# PicoCore-S3.net
KiCad netlist of a schematic drawn in Altium Designer
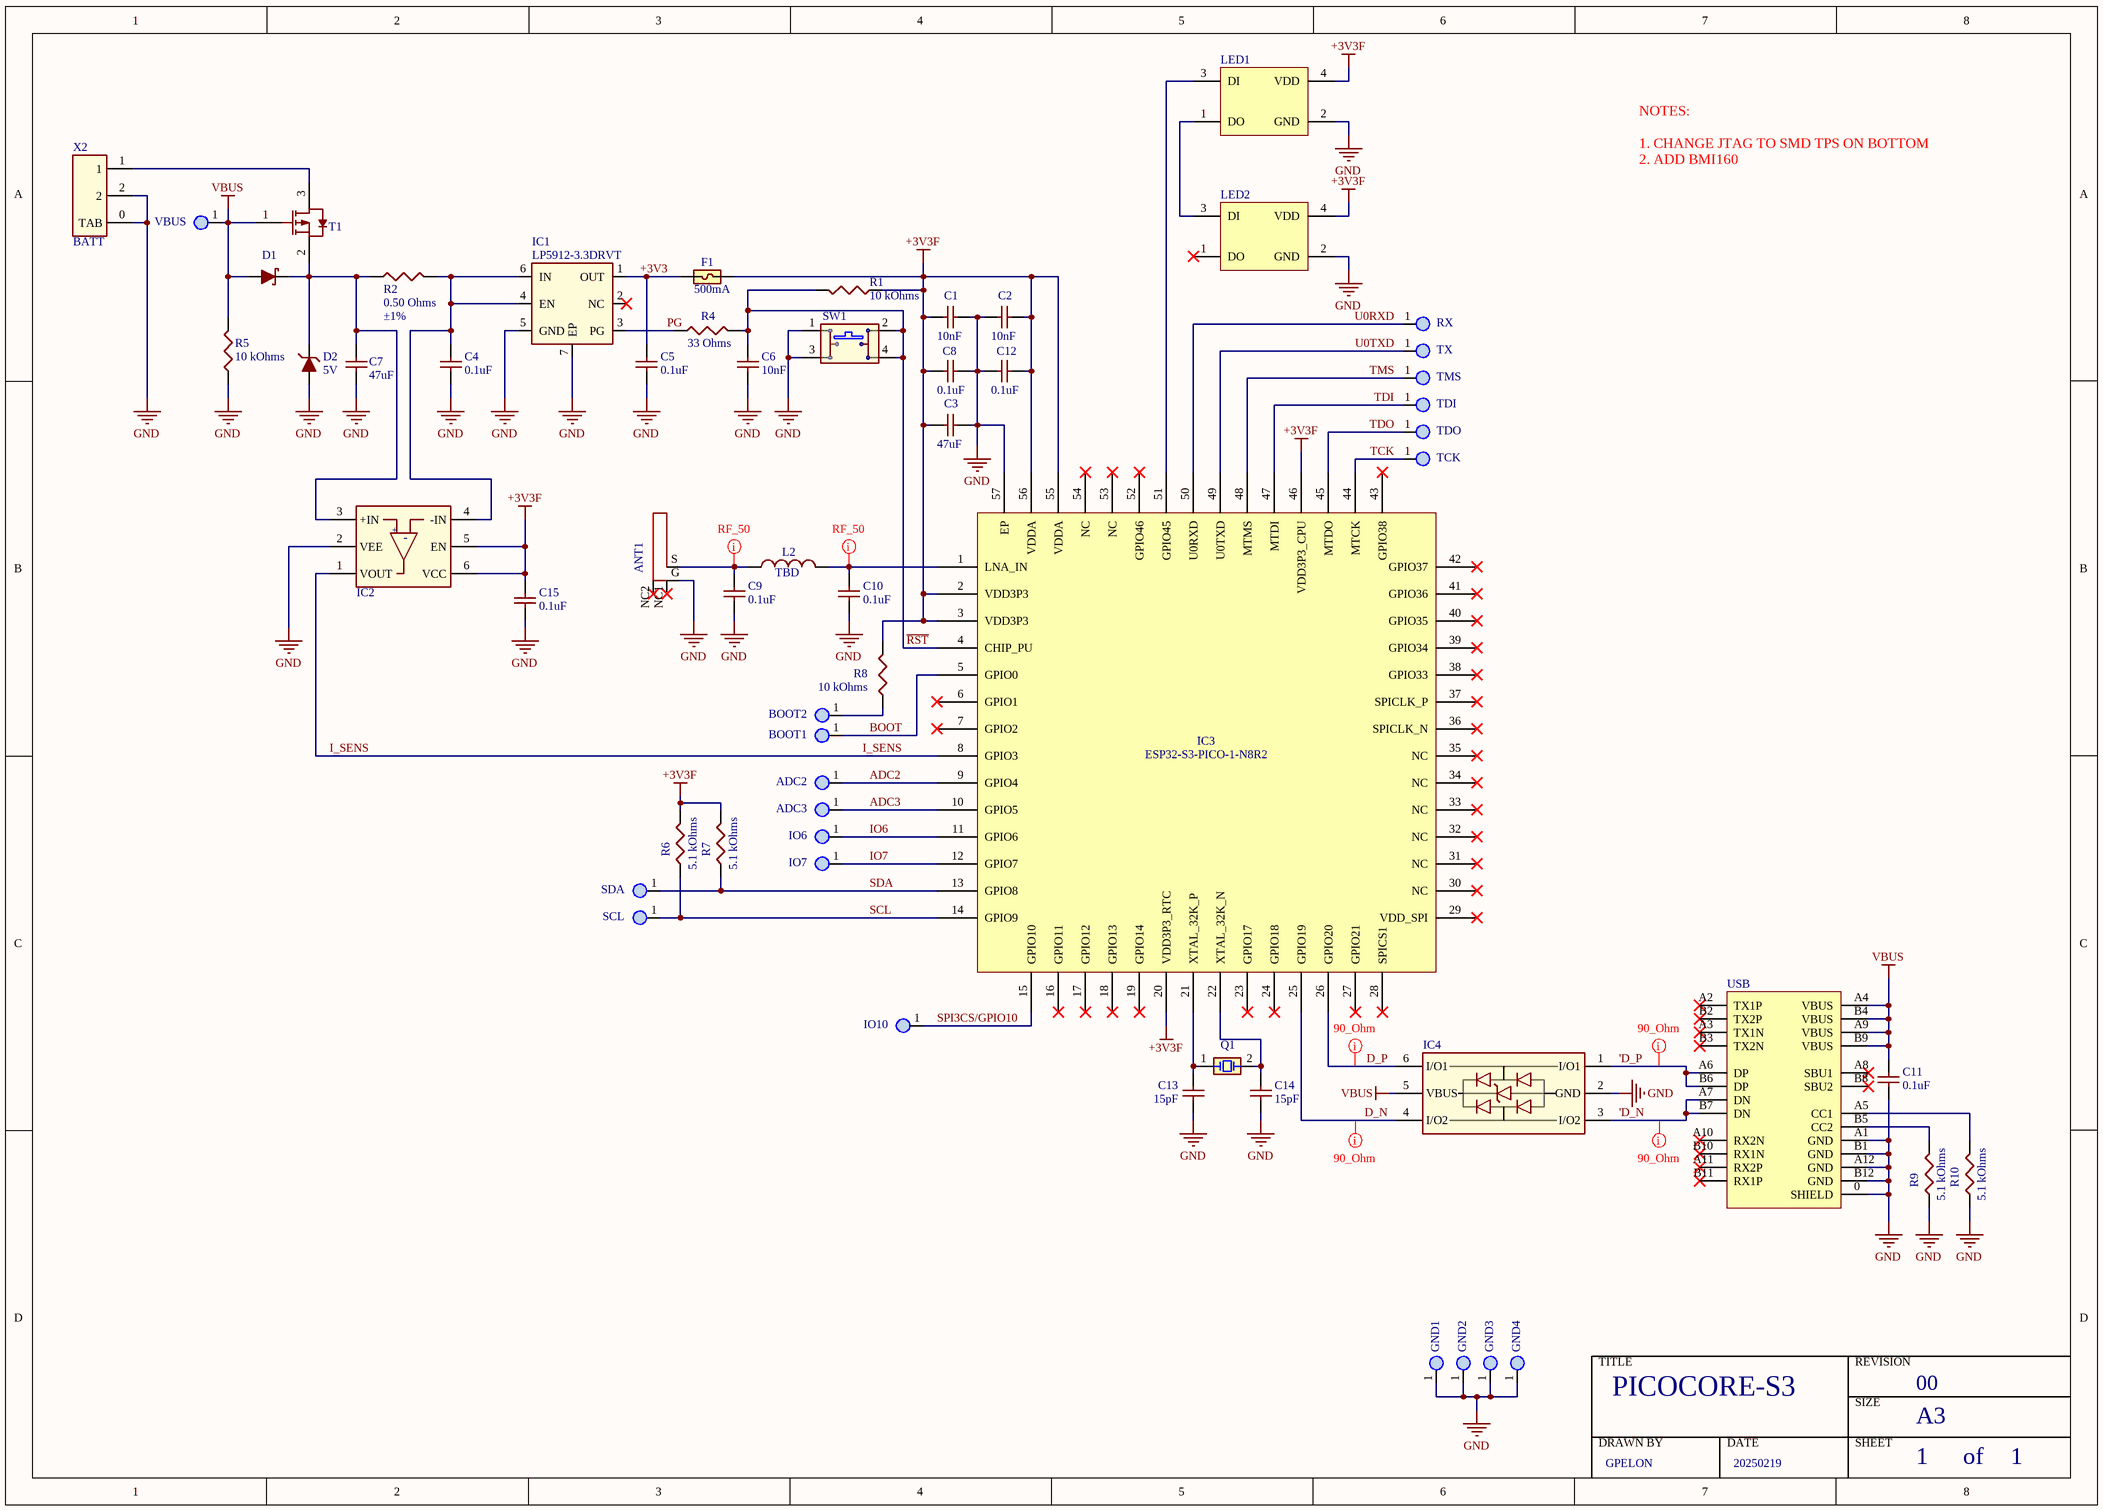
[diagram p0: PicoCore-S3.SchDoc]

(export (version "E")
  (design (tool "Eeschema 10.0.6"))
  (components
    (comp (ref "ADC2")
      (value "CASTELLATED PAD")
      (footprint "CASTELLATED PAD")
      (libsource (lib "PICOCORE-S3") (part "CASTELLATED_PAD"))
    )
    (comp (ref "ADC3")
      (value "CASTELLATED PAD")
      (footprint "CASTELLATED PAD")
      (libsource (lib "PICOCORE-S3") (part "CASTELLATED_PAD"))
    )
    (comp (ref "ANT1")
      (value "RF ANT 2.4GHZ STAMPED MET SLD")
      (footprint "PRO-OB-440")
      (description "RF ANTENNA Bluetooth, WirelessHART, WLAN, Zigbee™ Stamped Metal Solder Surface Mount")
      (fields (field (name "PRIMARY MANUFACTURER PART NUMBER") "PRO-OB-440"))
      (libsource (lib "PICOCORE-S3") (part "PRO-OB-440"))
    )
    (comp (ref "BOOT1")
      (value "CASTELLATED PAD")
      (footprint "CASTELLATED PAD")
      (libsource (lib "PICOCORE-S3") (part "CASTELLATED_PAD"))
    )
    (comp (ref "BOOT2")
      (value "CASTELLATED PAD")
      (footprint "CASTELLATED PAD")
      (libsource (lib "PICOCORE-S3") (part "CASTELLATED_PAD"))
    )
    (comp (ref "C1")
      (value "CAP NP")
      (footprint "CAP_0402_IPC")
      (description "CAP CER 10nF 10% 50V X7R 0402")
      (fields
        (field (name "PRIMARY MANUFACTURER PART NUMBER") "CGA2B3X7R1H103K050BB")
        (field (name "METHODE PART NUMBER") "18191XA86")
        (field (name "ELECTRICAL VALUE") "10nF")
      )
      (libsource (lib "MIL_DATABASE") (part "CAP NP"))
    )
    (comp (ref "C2")
      (value "CAP NP")
      (footprint "CAP_0402_IPC")
      (description "CAP CER 10nF 10% 50V X7R 0402")
      (fields
        (field (name "PRIMARY MANUFACTURER PART NUMBER") "CGA2B3X7R1H103K050BB")
        (field (name "METHODE PART NUMBER") "18191XA86")
        (field (name "ELECTRICAL VALUE") "10nF")
      )
      (libsource (lib "MIL_DATABASE") (part "CAP NP"))
    )
    (comp (ref "C3")
      (value "CAP NP")
      (footprint "CAP_1206_IPC")
      (description "Capacitor Ceramic 47UF 25V 20% X5R 1206")
      (fields
        (field (name "PRIMARY MANUFACTURER PART NUMBER") "C3216X5R1E476M160AC")
        (field (name "METHODE PART NUMBER") "TBD")
        (field (name "ELECTRICAL VALUE") "47uF")
      )
      (libsource (lib "MIL_DATABASE") (part "CAP NP"))
    )
    (comp (ref "C4")
      (value "CAP NP")
      (footprint "CAP_0402_IPC")
      (description "CAP CER 0.1uF 10% 50V X7R 0402")
      (fields
        (field (name "PRIMARY MANUFACTURER PART NUMBER") "GCM155R71H104KE02D")
        (field (name "METHODE PART NUMBER") "18191XA98")
        (field (name "ELECTRICAL VALUE") "0.1uF")
      )
      (libsource (lib "MIL_DATABASE") (part "CAP NP"))
    )
    (comp (ref "C5")
      (value "CAP NP")
      (footprint "CAP_0402_IPC")
      (description "CAP CER 0.1uF 10% 50V X7R 0402")
      (fields
        (field (name "PRIMARY MANUFACTURER PART NUMBER") "GCM155R71H104KE02D")
        (field (name "METHODE PART NUMBER") "18191XA98")
        (field (name "ELECTRICAL VALUE") "0.1uF")
      )
      (libsource (lib "MIL_DATABASE") (part "CAP NP"))
    )
    (comp (ref "C6")
      (value "CAP NP")
      (footprint "CAP_0402_IPC")
      (description "CAP CER 10nF 10% 50V X7R 0402")
      (fields
        (field (name "PRIMARY MANUFACTURER PART NUMBER") "CGA2B3X7R1H103K050BB")
        (field (name "METHODE PART NUMBER") "18191XA86")
        (field (name "ELECTRICAL VALUE") "10nF")
      )
      (libsource (lib "MIL_DATABASE") (part "CAP NP"))
    )
    (comp (ref "C7")
      (value "CAP NP")
      (footprint "CAP_1206_IPC")
      (description "Capacitor Ceramic 47UF 25V 20% X5R 1206")
      (fields
        (field (name "PRIMARY MANUFACTURER PART NUMBER") "C3216X5R1E476M160AC")
        (field (name "METHODE PART NUMBER") "TBD")
        (field (name "ELECTRICAL VALUE") "47uF")
      )
      (libsource (lib "MIL_DATABASE") (part "CAP NP"))
    )
    (comp (ref "C8")
      (value "CAP NP")
      (footprint "CAP_0402_IPC")
      (description "CAP CER 0.1uF 10% 50V X7R 0402")
      (fields
        (field (name "PRIMARY MANUFACTURER PART NUMBER") "GCM155R71H104KE02D")
        (field (name "METHODE PART NUMBER") "18191XA98")
        (field (name "ELECTRICAL VALUE") "0.1uF")
      )
      (libsource (lib "MIL_DATABASE") (part "CAP NP"))
    )
    (comp (ref "C9")
      (value "CAP NP")
      (footprint "CAP_0402_IPC")
      (description "CAP CER 0.1uF 10% 50V X7R 0402")
      (fields
        (field (name "PRIMARY MANUFACTURER PART NUMBER") "GCM155R71H104KE02D")
        (field (name "METHODE PART NUMBER") "18191XA98")
        (field (name "ELECTRICAL VALUE") "0.1uF")
      )
      (libsource (lib "MIL_DATABASE") (part "CAP NP"))
    )
    (comp (ref "C10")
      (value "CAP NP")
      (footprint "CAP_0402_IPC")
      (description "CAP CER 0.1uF 10% 50V X7R 0402")
      (fields
        (field (name "PRIMARY MANUFACTURER PART NUMBER") "GCM155R71H104KE02D")
        (field (name "METHODE PART NUMBER") "18191XA98")
        (field (name "ELECTRICAL VALUE") "0.1uF")
      )
      (libsource (lib "MIL_DATABASE") (part "CAP NP"))
    )
    (comp (ref "C11")
      (value "CAP NP")
      (footprint "CAP_0402_IPC")
      (description "CAP CER 0.1uF 10% 50V X7R 0402")
      (fields
        (field (name "PRIMARY MANUFACTURER PART NUMBER") "GCM155R71H104KE02D")
        (field (name "METHODE PART NUMBER") "18191XA98")
        (field (name "ELECTRICAL VALUE") "0.1uF")
      )
      (libsource (lib "MIL_DATABASE") (part "CAP NP"))
    )
    (comp (ref "C12")
      (value "CAP NP")
      (footprint "CAP_0402_IPC")
      (description "CAP CER 0.1uF 10% 50V X7R 0402")
      (fields
        (field (name "PRIMARY MANUFACTURER PART NUMBER") "GCM155R71H104KE02D")
        (field (name "METHODE PART NUMBER") "18191XA98")
        (field (name "ELECTRICAL VALUE") "0.1uF")
      )
      (libsource (lib "MIL_DATABASE") (part "CAP NP"))
    )
    (comp (ref "C13")
      (value "CAP NP")
      (footprint "CAP_0603_IPC")
      (description "Capacitor Ceramic NPO, SMT, 15PF, 50V, 5%, 0603")
      (fields
        (field (name "PRIMARY MANUFACTURER PART NUMBER") "C0603C150J5GACTU")
        (field (name "ELECTRICAL VALUE") "15pF")
      )
      (libsource (lib "MIL_DATABASE") (part "CAP NP"))
    )
    (comp (ref "C14")
      (value "CAP NP")
      (footprint "CAP_0603_IPC")
      (description "Capacitor Ceramic NPO, SMT, 15PF, 50V, 5%, 0603")
      (fields
        (field (name "PRIMARY MANUFACTURER PART NUMBER") "C0603C150J5GACTU")
        (field (name "ELECTRICAL VALUE") "15pF")
      )
      (libsource (lib "MIL_DATABASE") (part "CAP NP"))
    )
    (comp (ref "C15")
      (value "CAP NP")
      (footprint "CAP_0402_IPC")
      (description "CAP CER 0.1uF 10% 50V X7R 0402")
      (fields
        (field (name "PRIMARY MANUFACTURER PART NUMBER") "GCM155R71H104KE02D")
        (field (name "METHODE PART NUMBER") "18191XA98")
        (field (name "ELECTRICAL VALUE") "0.1uF")
      )
      (libsource (lib "MIL_DATABASE") (part "CAP NP"))
    )
    (comp (ref "D1")
      (value "DIODE_SCHOTTKY")
      (footprint "SOD-123_IPC")
      (description "DIODE SCHOTTKY 40V 500MA SOD123")
      (fields
        (field (name "PRIMARY MANUFACTURER PART NUMBER") "MBR0540-TP")
        (field (name "METHODE PART NUMBER") "TBD")
      )
      (libsource (lib "MIL_DATABASE") (part "DIODE_SCHOTTKY"))
    )
    (comp (ref "D2")
      (value "DIODE_TVS_UNI")
      (footprint "SOD-523_IPC")
      (description "Zener Diode, SMT, TVS, ESD, 5.0V, SOD-523")
      (fields
        (field (name "PRIMARY MANUFACTURER PART NUMBER") "ESD5Z5.0T1G")
        (field (name "METHODE PART NUMBER") "16441XA7")
        (field (name "ELECTRICAL VALUE") "5V")
      )
      (libsource (lib "MIL_DATABASE") (part "DIODE_TVS_UNI"))
    )
    (comp (ref "F1")
      (value "FUSE")
      (footprint "PTC_1206_IPC")
      (description "PTC RESET FUSE 24V 500MA 1206")
      (fields
        (field (name "PRIMARY MANUFACTURER PART NUMBER") "0ZCJ0050AF2E")
        (field (name "METHODE PART NUMBER") "TBD")
        (field (name "RATING1 VALUE") "500mA")
      )
      (libsource (lib "MIL_DATABASE") (part "FUSE"))
    )
    (comp (ref "GND1")
      (value "CASTELLATED PAD")
      (footprint "CASTELLATED PAD")
      (libsource (lib "PICOCORE-S3") (part "CASTELLATED_PAD"))
    )
    (comp (ref "GND2")
      (value "CASTELLATED PAD")
      (footprint "CASTELLATED PAD")
      (libsource (lib "PICOCORE-S3") (part "CASTELLATED_PAD"))
    )
    (comp (ref "GND3")
      (value "CASTELLATED PAD")
      (footprint "CASTELLATED PAD")
      (libsource (lib "PICOCORE-S3") (part "CASTELLATED_PAD"))
    )
    (comp (ref "GND4")
      (value "CASTELLATED PAD")
      (footprint "CASTELLATED PAD")
      (libsource (lib "PICOCORE-S3") (part "CASTELLATED_PAD"))
    )
    (comp (ref "IC1")
      (value "LP5912-3.3")
      (footprint "SON6_0P65_EP_IPC")
      (description "IC REG LDO 3.3V 0.5A 6SON")
      (fields
        (field (name "PRIMARY MANUFACTURER PART NUMBER") "LP5912-3.3DRVT")
        (field (name "METHODE PART NUMBER") "TBD")
      )
      (libsource (lib "MIL_DATABASE") (part "LP5912-3.3"))
    )
    (comp (ref "IC2")
      (value "NCV2002SN2T1")
      (footprint "TSOP6_0P95_IPC")
      (description "IC OPAMP 1-CIRCUIT RAIL-TO-RAIL TSOP-6")
      (fields
        (field (name "PRIMARY MANUFACTURER PART NUMBER") "NCV2002SN2T1G")
        (field (name "METHODE PART NUMBER") "16455XA64")
      )
      (libsource (lib "MIL_DATABASE") (part "NCV2002SN2T1"))
    )
    (comp (ref "IC3")
      (value "RF TXRX MOD BLUETOOTH WIFISMD")
      (footprint "LGA56")
      (fields (field (name "PRIMARY MANUFACTURER PART NUMBER") "ESP32-S3-PICO-1-N8R2"))
      (libsource (lib "PICOCORE-S3") (part "ESP32-S3-PICO-1-N8R2"))
    )
    (comp (ref "IC4")
      (value "USBLC6-2P6")
      (footprint "SOT666_IPC")
      (description "TVS DIODE 5.25V 17VC SOT-666")
      (fields (field (name "METHODE PART NUMBER") "TBD"))
      (libsource (lib "MIL_DATABASE") (part "USBLC6-2P6"))
    )
    (comp (ref "IO6")
      (value "CASTELLATED PAD")
      (footprint "CASTELLATED PAD")
      (libsource (lib "PICOCORE-S3") (part "CASTELLATED_PAD"))
    )
    (comp (ref "IO7")
      (value "CASTELLATED PAD")
      (footprint "CASTELLATED PAD")
      (libsource (lib "PICOCORE-S3") (part "CASTELLATED_PAD"))
    )
    (comp (ref "IO10")
      (value "CASTELLATED PAD")
      (footprint "CASTELLATED PAD")
      (libsource (lib "PICOCORE-S3") (part "CASTELLATED_PAD"))
    )
    (comp (ref "L2")
      (value "TBD")
      (footprint "IND_0805_IPC")
      (description "CHIP BEAD 1K OHM 600mA 0805")
      (fields (field (name "PRIMARY MANUFACTURER PART NUMBER") "BLM21AG102SN1D"))
      (libsource (lib "MIL_DATABASE") (part "IND"))
    )
    (comp (ref "LED1")
      (value "ADDRESS LED DISCRETE RGB")
      (footprint "WS2812B-2020")
      (description "Addressable Lighting Neopixel 10 LED Discrete Red, Green, Blue (RGB) 2.00mm L x 2.00mm W")
      (libsource (lib "PICOCORE-S3") (part "WS2812B-2020"))
    )
    (comp (ref "LED2")
      (value "ADDRESS LED DISCRETE RGB")
      (footprint "WS2812B-2020")
      (description "Addressable Lighting Neopixel 10 LED Discrete Red, Green, Blue (RGB) 2.00mm L x 2.00mm W")
      (libsource (lib "PICOCORE-S3") (part "WS2812B-2020"))
    )
    (comp (ref "Q1")
      (value "CRYSTAL_H_2PIN")
      (footprint "XTAL_ECX-34Q")
      (description "CRYSTAL 32.768KHZ 12.5PF SMD-2")
      (fields
        (field (name "PRIMARY MANUFACTURER PART NUMBER") "ECS-.327-12.5-34R-C-TR")
        (field (name "METHODE PART NUMBER") "TBD")
      )
      (libsource (lib "MIL_DATABASE") (part "CRYSTAL_H_2PIN"))
    )
    (comp (ref "R1")
      (value "RES")
      (footprint "RES_0402_IPC")
      (description "RES SMD 10K OHM 1% 1/16W 0402")
      (fields
        (field (name "PRIMARY MANUFACTURER PART NUMBER") "RC0402FR-0710KL")
        (field (name "METHODE PART NUMBER") "TBD")
        (field (name "ELECTRICAL VALUE") "10 kOhms")
      )
      (libsource (lib "MIL_DATABASE") (part "RES"))
    )
    (comp (ref "R2")
      (value "RES")
      (footprint "RES_1206_IPC")
      (description "RES SMD 0.250 OHM 1% 1/2W 1206")
      (fields
        (field (name "PRIMARY MANUFACTURER PART NUMBER") "CSR1206FTR500")
        (field (name "METHODE PART NUMBER") "TBD_0E24")
        (field (name "ELECTRICAL VALUE") "0.50 Ohms")
        (field (name "TOLERANCE %") "±1%")
      )
      (libsource (lib "MIL_DATABASE") (part "RES"))
    )
    (comp (ref "R4")
      (value "RES")
      (footprint "RES_0402_IPC")
      (description "RES SMD 33 OHM 1% 1/10W 0402")
      (fields
        (field (name "PRIMARY MANUFACTURER PART NUMBER") "RK73H1ETTP33R0F")
        (field (name "METHODE PART NUMBER") "TBD")
        (field (name "ELECTRICAL VALUE") "33 Ohms")
      )
      (libsource (lib "MIL_DATABASE") (part "RES"))
    )
    (comp (ref "R5")
      (value "RES")
      (footprint "RES_0402_IPC")
      (description "RES SMD 10K OHM 1% 1/16W 0402")
      (fields
        (field (name "PRIMARY MANUFACTURER PART NUMBER") "RC0402FR-0710KL")
        (field (name "METHODE PART NUMBER") "TBD")
        (field (name "ELECTRICAL VALUE") "10 kOhms")
      )
      (libsource (lib "MIL_DATABASE") (part "RES"))
    )
    (comp (ref "R6")
      (value "RES")
      (footprint "RES_0402_IPC")
      (description "RES SMD 5.1K OHM 1% 1/16W 0402")
      (fields
        (field (name "PRIMARY MANUFACTURER PART NUMBER") "RC0402FR-075K1L")
        (field (name "METHODE PART NUMBER") "TBD")
        (field (name "ELECTRICAL VALUE") "5.1 kOhms")
      )
      (libsource (lib "MIL_DATABASE") (part "RES"))
    )
    (comp (ref "R7")
      (value "RES")
      (footprint "RES_0402_IPC")
      (description "RES SMD 5.1K OHM 1% 1/16W 0402")
      (fields
        (field (name "PRIMARY MANUFACTURER PART NUMBER") "RC0402FR-075K1L")
        (field (name "METHODE PART NUMBER") "TBD")
        (field (name "ELECTRICAL VALUE") "5.1 kOhms")
      )
      (libsource (lib "MIL_DATABASE") (part "RES"))
    )
    (comp (ref "R8")
      (value "RES")
      (footprint "RES_0402_IPC")
      (description "RES SMD 10K OHM 1% 1/16W 0402")
      (fields
        (field (name "PRIMARY MANUFACTURER PART NUMBER") "RC0402FR-0710KL")
        (field (name "METHODE PART NUMBER") "TBD")
        (field (name "ELECTRICAL VALUE") "10 kOhms")
      )
      (libsource (lib "MIL_DATABASE") (part "RES"))
    )
    (comp (ref "R9")
      (value "RES")
      (footprint "RES_0402_IPC")
      (description "RES SMD 5.1K OHM 1% 1/16W 0402")
      (fields
        (field (name "PRIMARY MANUFACTURER PART NUMBER") "RC0402FR-075K1L")
        (field (name "METHODE PART NUMBER") "TBD")
        (field (name "ELECTRICAL VALUE") "5.1 kOhms")
      )
      (libsource (lib "MIL_DATABASE") (part "RES"))
    )
    (comp (ref "R10")
      (value "RES")
      (footprint "RES_0402_IPC")
      (description "RES SMD 5.1K OHM 1% 1/16W 0402")
      (fields
        (field (name "PRIMARY MANUFACTURER PART NUMBER") "RC0402FR-075K1L")
        (field (name "METHODE PART NUMBER") "TBD")
        (field (name "ELECTRICAL VALUE") "5.1 kOhms")
      )
      (libsource (lib "MIL_DATABASE") (part "RES"))
    )
    (comp (ref "RX")
      (value "CASTELLATED PAD")
      (footprint "CASTELLATED PAD")
      (libsource (lib "PICOCORE-S3") (part "CASTELLATED_PAD"))
    )
    (comp (ref "SCL")
      (value "CASTELLATED PAD")
      (footprint "CASTELLATED PAD")
      (libsource (lib "PICOCORE-S3") (part "CASTELLATED_PAD"))
    )
    (comp (ref "SDA")
      (value "CASTELLATED PAD")
      (footprint "CASTELLATED PAD")
      (libsource (lib "PICOCORE-S3") (part "CASTELLATED_PAD"))
    )
    (comp (ref "SW1")
      (value "SW-RESET")
      (footprint "SW_KMR231GLFS")
      (description "SWITCH TACTILE SPST-NO 0.05A 32V")
      (fields
        (field (name "PRIMARY MANUFACTURER PART NUMBER") "KMR231GLFS")
        (field (name "METHODE PART NUMBER") "TBD")
      )
      (libsource (lib "MIL_DATABASE") (part "SW-RESET"))
    )
    (comp (ref "T1")
      (value "MOSFET_P-CH")
      (footprint "SOT23-3_IPC")
      (description "MOSFET P-CH 20V 3.7A SOT-23")
      (fields
        (field (name "PRIMARY MANUFACTURER PART NUMBER") "IRLML6402TRPBF")
        (field (name "METHODE PART NUMBER") "TBD")
      )
      (libsource (lib "MIL_DATABASE") (part "MOSFET_P-CH"))
    )
    (comp (ref "TCK")
      (value "CASTELLATED PAD")
      (footprint "CASTELLATED PAD")
      (libsource (lib "PICOCORE-S3") (part "CASTELLATED_PAD"))
    )
    (comp (ref "TDI")
      (value "CASTELLATED PAD")
      (footprint "CASTELLATED PAD")
      (libsource (lib "PICOCORE-S3") (part "CASTELLATED_PAD"))
    )
    (comp (ref "TDO")
      (value "CASTELLATED PAD")
      (footprint "CASTELLATED PAD")
      (libsource (lib "PICOCORE-S3") (part "CASTELLATED_PAD"))
    )
    (comp (ref "TMS")
      (value "CASTELLATED PAD")
      (footprint "CASTELLATED PAD")
      (libsource (lib "PICOCORE-S3") (part "CASTELLATED_PAD"))
    )
    (comp (ref "TX")
      (value "CASTELLATED PAD")
      (footprint "CASTELLATED PAD")
      (libsource (lib "PICOCORE-S3") (part "CASTELLATED_PAD"))
    )
    (comp (ref "USB")
      (value "CONN RCP USB3.1 TYPEC 24P SMD RA")
      (footprint "12401832E402A")
      (fields (field (name "PRIMARY MANUFACTURER PART NUMBER") "12401832E402A"))
      (libsource (lib "PICOCORE-S3") (part "12401832E402A"))
    )
    (comp (ref "VBUS")
      (value "CASTELLATED PAD")
      (footprint "CASTELLATED PAD")
      (libsource (lib "PICOCORE-S3") (part "CASTELLATED_PAD"))
    )
    (comp (ref "X2")
      (value "BATT")
      (footprint "CONN_2POS_SM02B")
      (description "CONN HEADER R/A 2POS 1.25mm SMD")
      (fields
        (field (name "PRIMARY MANUFACTURER PART NUMBER") "SM02B-GHS-TB(LF)(SN)")
        (field (name "METHODE PART NUMBER") "TBD")
      )
      (libsource (lib "HET_DATABASE") (part "CONN_2POS_TAB"))
    )
  )
  (nets
    (net (code "1") (name "+3V3F") (class "Default")
      (node (ref "C1") (pin "2") (pinfunction "2_2") (pintype "passive"))
      (node (ref "C12") (pin "1") (pinfunction "1_1") (pintype "passive"))
      (node (ref "C15") (pin "2") (pinfunction "2_2") (pintype "passive"))
      (node (ref "C2") (pin "1") (pinfunction "1_1") (pintype "passive"))
      (node (ref "C3") (pin "2") (pinfunction "2_2") (pintype "passive"))
      (node (ref "C8") (pin "2") (pinfunction "2_2") (pintype "passive"))
      (node (ref "F1") (pin "2") (pinfunction "2_2") (pintype "passive"))
      (node (ref "IC2") (pin "5") (pinfunction "EN_5") (pintype "passive"))
      (node (ref "IC2") (pin "6") (pinfunction "VCC_6") (pintype "passive"))
      (node (ref "IC3") (pin "2") (pinfunction "VDD3P3_2") (pintype "passive"))
      (node (ref "IC3") (pin "20") (pinfunction "VDD3P3_RTC_20") (pintype "passive"))
      (node (ref "IC3") (pin "3") (pinfunction "VDD3P3_3") (pintype "passive"))
      (node (ref "IC3") (pin "46") (pinfunction "VDD3P3_CPU_46") (pintype "passive"))
      (node (ref "IC3") (pin "55") (pinfunction "VDDA_55") (pintype "passive"))
      (node (ref "IC3") (pin "56") (pinfunction "VDDA_56") (pintype "passive"))
      (node (ref "LED1") (pin "4") (pinfunction "VDD_4") (pintype "passive"))
      (node (ref "LED2") (pin "4") (pinfunction "VDD_4") (pintype "passive"))
      (node (ref "R1") (pin "1") (pinfunction "1_1") (pintype "passive"))
      (node (ref "R6") (pin "2") (pinfunction "2_2") (pintype "passive"))
      (node (ref "R7") (pin "2") (pinfunction "2_2") (pintype "passive"))
      (node (ref "R8") (pin "2") (pinfunction "2_2") (pintype "passive"))
    )
    (net (code "2") (name "/'D_N") (class "Default")
      (node (ref "IC4") (pin "3") (pinfunction "I/O2_3") (pintype "passive"))
      (node (ref "USB") (pin "A7") (pinfunction "DN_A7") (pintype "passive"))
      (node (ref "USB") (pin "B7") (pinfunction "DN_B7") (pintype "passive"))
    )
    (net (code "3") (name "/'D_P") (class "Default")
      (node (ref "IC4") (pin "1") (pinfunction "I/O1_1") (pintype "passive"))
      (node (ref "USB") (pin "A6") (pinfunction "DP_A6") (pintype "passive"))
      (node (ref "USB") (pin "B6") (pinfunction "DP_B6") (pintype "passive"))
    )
    (net (code "4") (name "/+3V3") (class "Default")
      (node (ref "C5") (pin "2") (pinfunction "2_2") (pintype "passive"))
      (node (ref "F1") (pin "1") (pinfunction "1_1") (pintype "passive"))
      (node (ref "IC1") (pin "1") (pinfunction "OUT_1") (pintype "passive"))
    )
    (net (code "5") (name "/ADC2") (class "Default")
      (node (ref "ADC2") (pin "1") (pinfunction "1_1") (pintype "passive"))
      (node (ref "IC3") (pin "9") (pinfunction "GPIO4_9") (pintype "passive"))
    )
    (net (code "6") (name "/ADC3") (class "Default")
      (node (ref "ADC3") (pin "1") (pinfunction "1_1") (pintype "passive"))
      (node (ref "IC3") (pin "10") (pinfunction "GPIO5_10") (pintype "passive"))
    )
    (net (code "7") (name "/BOOT") (class "Default")
      (node (ref "BOOT1") (pin "1") (pinfunction "1_1") (pintype "passive"))
      (node (ref "IC3") (pin "5") (pinfunction "GPIO0_5") (pintype "passive"))
    )
    (net (code "8") (name "/D_N") (class "Default")
      (node (ref "IC3") (pin "25") (pinfunction "GPIO19_25") (pintype "passive"))
      (node (ref "IC4") (pin "4") (pinfunction "I/O2_4") (pintype "passive"))
    )
    (net (code "9") (name "/D_P") (class "Default")
      (node (ref "IC3") (pin "26") (pinfunction "GPIO20_26") (pintype "passive"))
      (node (ref "IC4") (pin "6") (pinfunction "I/O1_6") (pintype "passive"))
    )
    (net (code "10") (name "/IO6") (class "Default")
      (node (ref "IC3") (pin "11") (pinfunction "GPIO6_11") (pintype "passive"))
      (node (ref "IO6") (pin "1") (pinfunction "1_1") (pintype "passive"))
    )
    (net (code "11") (name "/IO7") (class "Default")
      (node (ref "IC3") (pin "12") (pinfunction "GPIO7_12") (pintype "passive"))
      (node (ref "IO7") (pin "1") (pinfunction "1_1") (pintype "passive"))
    )
    (net (code "12") (name "/I_SENS") (class "Default")
      (node (ref "IC2") (pin "1") (pinfunction "VOUT_1") (pintype "passive"))
      (node (ref "IC3") (pin "8") (pinfunction "GPIO3_8") (pintype "passive"))
    )
    (net (code "13") (name "/PG") (class "Default")
      (node (ref "IC1") (pin "3") (pinfunction "PG_3") (pintype "passive"))
      (node (ref "R4") (pin "1") (pinfunction "1_1") (pintype "passive"))
    )
    (net (code "14") (name "/SCL") (class "Default")
      (node (ref "IC3") (pin "14") (pinfunction "GPIO9_14") (pintype "passive"))
      (node (ref "R6") (pin "1") (pinfunction "1_1") (pintype "passive"))
      (node (ref "SCL") (pin "1") (pinfunction "1_1") (pintype "passive"))
    )
    (net (code "15") (name "/SDA") (class "Default")
      (node (ref "IC3") (pin "13") (pinfunction "GPIO8_13") (pintype "passive"))
      (node (ref "R7") (pin "1") (pinfunction "1_1") (pintype "passive"))
      (node (ref "SDA") (pin "1") (pinfunction "1_1") (pintype "passive"))
    )
    (net (code "16") (name "/SPI3CS{slash}GPIO10") (class "Default")
      (node (ref "IC3") (pin "15") (pinfunction "GPIO10_15") (pintype "passive"))
      (node (ref "IO10") (pin "1") (pinfunction "1_1") (pintype "passive"))
    )
    (net (code "17") (name "/TCK") (class "Default")
      (node (ref "IC3") (pin "44") (pinfunction "MTCK_44") (pintype "passive"))
      (node (ref "TCK") (pin "1") (pinfunction "1_1") (pintype "passive"))
    )
    (net (code "18") (name "/TDI") (class "Default")
      (node (ref "IC3") (pin "47") (pinfunction "MTDI_47") (pintype "passive"))
      (node (ref "TDI") (pin "1") (pinfunction "1_1") (pintype "passive"))
    )
    (net (code "19") (name "/TDO") (class "Default")
      (node (ref "IC3") (pin "45") (pinfunction "MTDO_45") (pintype "passive"))
      (node (ref "TDO") (pin "1") (pinfunction "1_1") (pintype "passive"))
    )
    (net (code "20") (name "/TMS") (class "Default")
      (node (ref "IC3") (pin "48") (pinfunction "MTMS_48") (pintype "passive"))
      (node (ref "TMS") (pin "1") (pinfunction "1_1") (pintype "passive"))
    )
    (net (code "21") (name "/U0RXD") (class "Default")
      (node (ref "IC3") (pin "50") (pinfunction "U0RXD_50") (pintype "passive"))
      (node (ref "RX") (pin "1") (pinfunction "1_1") (pintype "passive"))
    )
    (net (code "22") (name "/U0TXD") (class "Default")
      (node (ref "IC3") (pin "49") (pinfunction "U0TXD_49") (pintype "passive"))
      (node (ref "TX") (pin "1") (pinfunction "1_1") (pintype "passive"))
    )
    (net (code "23") (name "/~{RST}") (class "Default")
      (node (ref "C6") (pin "1") (pinfunction "1_1") (pintype "passive"))
      (node (ref "IC3") (pin "4") (pinfunction "CHIP_PU_4") (pintype "passive"))
      (node (ref "R1") (pin "2") (pinfunction "2_2") (pintype "passive"))
      (node (ref "R4") (pin "2") (pinfunction "2_2") (pintype "passive"))
      (node (ref "SW1") (pin "2") (pinfunction "2_2") (pintype "passive"))
      (node (ref "SW1") (pin "4") (pinfunction "4_4") (pintype "passive"))
    )
    (net (code "24") (name "GND") (class "Default")
      (node (ref "ANT1") (pin "G") (pintype "passive"))
      (node (ref "C1") (pin "1") (pinfunction "1_1") (pintype "passive"))
      (node (ref "C10") (pin "1") (pinfunction "1_1") (pintype "passive"))
      (node (ref "C11") (pin "1") (pinfunction "1_1") (pintype "passive"))
      (node (ref "C12") (pin "2") (pinfunction "2_2") (pintype "passive"))
      (node (ref "C13") (pin "1") (pinfunction "1_1") (pintype "passive"))
      (node (ref "C14") (pin "1") (pinfunction "1_1") (pintype "passive"))
      (node (ref "C15") (pin "1") (pinfunction "1_1") (pintype "passive"))
      (node (ref "C2") (pin "2") (pinfunction "2_2") (pintype "passive"))
      (node (ref "C3") (pin "1") (pinfunction "1_1") (pintype "passive"))
      (node (ref "C4") (pin "1") (pinfunction "1_1") (pintype "passive"))
      (node (ref "C5") (pin "1") (pinfunction "1_1") (pintype "passive"))
      (node (ref "C6") (pin "2") (pinfunction "2_2") (pintype "passive"))
      (node (ref "C7") (pin "2") (pinfunction "2_2") (pintype "passive"))
      (node (ref "C8") (pin "1") (pinfunction "1_1") (pintype "passive"))
      (node (ref "C9") (pin "1") (pinfunction "1_1") (pintype "passive"))
      (node (ref "D2") (pin "2") (pinfunction "A_2") (pintype "passive"))
      (node (ref "GND1") (pin "1") (pinfunction "1_1") (pintype "passive"))
      (node (ref "GND2") (pin "1") (pinfunction "1_1") (pintype "passive"))
      (node (ref "GND3") (pin "1") (pinfunction "1_1") (pintype "passive"))
      (node (ref "GND4") (pin "1") (pinfunction "1_1") (pintype "passive"))
      (node (ref "IC1") (pin "5") (pinfunction "GND_5") (pintype "passive"))
      (node (ref "IC1") (pin "7") (pinfunction "EP_7") (pintype "passive"))
      (node (ref "IC2") (pin "2") (pinfunction "VEE_2") (pintype "passive"))
      (node (ref "IC3") (pin "57") (pinfunction "EP_57") (pintype "passive"))
      (node (ref "IC4") (pin "2") (pinfunction "GND_2") (pintype "passive"))
      (node (ref "LED1") (pin "2") (pinfunction "GND_2") (pintype "passive"))
      (node (ref "LED2") (pin "2") (pinfunction "GND_2") (pintype "passive"))
      (node (ref "R10") (pin "1") (pinfunction "1_1") (pintype "passive"))
      (node (ref "R5") (pin "1") (pinfunction "1_1") (pintype "passive"))
      (node (ref "R9") (pin "1") (pinfunction "1_1") (pintype "passive"))
      (node (ref "SW1") (pin "1") (pinfunction "1_1") (pintype "passive"))
      (node (ref "SW1") (pin "3") (pinfunction "3_3") (pintype "passive"))
      (node (ref "USB") (pin "0") (pinfunction "SHIELD_0") (pintype "passive"))
      (node (ref "USB") (pin "A1") (pinfunction "GND_A1") (pintype "passive"))
      (node (ref "USB") (pin "A12") (pinfunction "GND_A12") (pintype "passive"))
      (node (ref "USB") (pin "B1") (pinfunction "GND_B1") (pintype "passive"))
      (node (ref "USB") (pin "B12") (pinfunction "GND_B12") (pintype "passive"))
      (node (ref "X2") (pin "0") (pinfunction "TAB_0") (pintype "passive"))
      (node (ref "X2") (pin "2") (pinfunction "2_2") (pintype "passive"))
    )
    (net (code "25") (name "Net-(ANT1-PadS)") (class "Default")
      (node (ref "ANT1") (pin "S") (pintype "passive"))
      (node (ref "C9") (pin "2") (pinfunction "2_2") (pintype "passive"))
      (node (ref "L2") (pin "1") (pinfunction "1_1") (pintype "passive"))
    )
    (net (code "26") (name "Net-(BOOT2-Pad1)") (class "Default")
      (node (ref "BOOT2") (pin "1") (pinfunction "1_1") (pintype "passive"))
      (node (ref "R8") (pin "1") (pinfunction "1_1") (pintype "passive"))
    )
    (net (code "27") (name "Net-(D1-K)") (class "Default")
      (node (ref "C7") (pin "1") (pinfunction "1_1") (pintype "passive"))
      (node (ref "D1") (pin "1") (pinfunction "K_1") (pintype "passive"))
      (node (ref "D2") (pin "1") (pinfunction "K_1") (pintype "passive"))
      (node (ref "IC2") (pin "3") (pinfunction "+IN_3") (pintype "passive"))
      (node (ref "R2") (pin "1") (pinfunction "1_1") (pintype "passive"))
      (node (ref "T1") (pin "2") (pinfunction "S_2") (pintype "passive"))
    )
    (net (code "28") (name "Net-(IC1-EN)") (class "Default")
      (node (ref "C4") (pin "2") (pinfunction "2_2") (pintype "passive"))
      (node (ref "IC1") (pin "4") (pinfunction "EN_4") (pintype "passive"))
      (node (ref "IC1") (pin "6") (pinfunction "IN_6") (pintype "passive"))
      (node (ref "IC2") (pin "4") (pinfunction "-IN_4") (pintype "passive"))
      (node (ref "R2") (pin "2") (pinfunction "2_2") (pintype "passive"))
    )
    (net (code "29") (name "Net-(IC3-GPIO45)") (class "Default")
      (node (ref "IC3") (pin "51") (pinfunction "GPIO45_51") (pintype "passive"))
      (node (ref "LED1") (pin "3") (pinfunction "DI_3") (pintype "passive"))
    )
    (net (code "30") (name "Net-(IC3-LNA_IN)") (class "Default")
      (node (ref "C10") (pin "2") (pinfunction "2_2") (pintype "passive"))
      (node (ref "IC3") (pin "1") (pinfunction "LNA_IN_1") (pintype "passive"))
      (node (ref "L2") (pin "2") (pinfunction "2_2") (pintype "passive"))
    )
    (net (code "31") (name "Net-(IC3-XTAL_32K_N)") (class "Default")
      (node (ref "C14") (pin "2") (pinfunction "2_2") (pintype "passive"))
      (node (ref "IC3") (pin "22") (pinfunction "XTAL_32K_N_22") (pintype "passive"))
      (node (ref "Q1") (pin "2") (pinfunction "I/O@2_2") (pintype "passive"))
    )
    (net (code "32") (name "Net-(IC3-XTAL_32K_P)") (class "Default")
      (node (ref "C13") (pin "2") (pinfunction "2_2") (pintype "passive"))
      (node (ref "IC3") (pin "21") (pinfunction "XTAL_32K_P_21") (pintype "passive"))
      (node (ref "Q1") (pin "1") (pinfunction "I/O@1_1") (pintype "passive"))
    )
    (net (code "33") (name "Net-(LED1-DO)") (class "Default")
      (node (ref "LED1") (pin "1") (pinfunction "DO_1") (pintype "passive"))
      (node (ref "LED2") (pin "3") (pinfunction "DI_3") (pintype "passive"))
    )
    (net (code "34") (name "Net-(T1-D)") (class "Default")
      (node (ref "T1") (pin "3") (pinfunction "D_3") (pintype "passive"))
      (node (ref "X2") (pin "1") (pinfunction "1_1") (pintype "passive"))
    )
    (net (code "35") (name "Net-(USB-CC1)") (class "Default")
      (node (ref "R10") (pin "2") (pinfunction "2_2") (pintype "passive"))
      (node (ref "USB") (pin "A5") (pinfunction "CC1_A5") (pintype "passive"))
    )
    (net (code "36") (name "Net-(USB-CC2)") (class "Default")
      (node (ref "R9") (pin "2") (pinfunction "2_2") (pintype "passive"))
      (node (ref "USB") (pin "B5") (pinfunction "CC2_B5") (pintype "passive"))
    )
    (net (code "37") (name "VBUS") (class "Default")
      (node (ref "C11") (pin "2") (pinfunction "2_2") (pintype "passive"))
      (node (ref "D1") (pin "2") (pinfunction "A_2") (pintype "passive"))
      (node (ref "IC4") (pin "5") (pinfunction "VBUS_5") (pintype "passive"))
      (node (ref "R5") (pin "2") (pinfunction "2_2") (pintype "passive"))
      (node (ref "T1") (pin "1") (pinfunction "G_1") (pintype "passive"))
      (node (ref "USB") (pin "A4") (pinfunction "VBUS_A4") (pintype "passive"))
      (node (ref "USB") (pin "A9") (pinfunction "VBUS_A9") (pintype "passive"))
      (node (ref "USB") (pin "B4") (pinfunction "VBUS_B4") (pintype "passive"))
      (node (ref "USB") (pin "B9") (pinfunction "VBUS_B9") (pintype "passive"))
      (node (ref "VBUS") (pin "1") (pinfunction "1_1") (pintype "passive"))
    )
    (net (code "38") (name "unconnected-(ANT1-PadNC1)") (class "Default")
      (node (ref "ANT1") (pin "NC1") (pintype "passive+no_connect"))
    )
    (net (code "39") (name "unconnected-(ANT1-PadNC2)") (class "Default")
      (node (ref "ANT1") (pin "NC2") (pintype "passive+no_connect"))
    )
    (net (code "40") (name "unconnected-(IC1-NC-Pad2)") (class "Default")
      (node (ref "IC1") (pin "2") (pinfunction "NC_2") (pintype "passive+no_connect"))
    )
    (net (code "41") (name "unconnected-(IC3-GPIO1-Pad6)") (class "Default")
      (node (ref "IC3") (pin "6") (pinfunction "GPIO1_6") (pintype "passive+no_connect"))
    )
    (net (code "42") (name "unconnected-(IC3-GPIO2-Pad7)") (class "Default")
      (node (ref "IC3") (pin "7") (pinfunction "GPIO2_7") (pintype "passive+no_connect"))
    )
    (net (code "43") (name "unconnected-(IC3-GPIO11-Pad16)") (class "Default")
      (node (ref "IC3") (pin "16") (pinfunction "GPIO11_16") (pintype "passive+no_connect"))
    )
    (net (code "44") (name "unconnected-(IC3-GPIO12-Pad17)") (class "Default")
      (node (ref "IC3") (pin "17") (pinfunction "GPIO12_17") (pintype "passive+no_connect"))
    )
    (net (code "45") (name "unconnected-(IC3-GPIO13-Pad18)") (class "Default")
      (node (ref "IC3") (pin "18") (pinfunction "GPIO13_18") (pintype "passive+no_connect"))
    )
    (net (code "46") (name "unconnected-(IC3-GPIO14-Pad19)") (class "Default")
      (node (ref "IC3") (pin "19") (pinfunction "GPIO14_19") (pintype "passive+no_connect"))
    )
    (net (code "47") (name "unconnected-(IC3-GPIO17-Pad23)") (class "Default")
      (node (ref "IC3") (pin "23") (pinfunction "GPIO17_23") (pintype "passive+no_connect"))
    )
    (net (code "48") (name "unconnected-(IC3-GPIO18-Pad24)") (class "Default")
      (node (ref "IC3") (pin "24") (pinfunction "GPIO18_24") (pintype "passive+no_connect"))
    )
    (net (code "49") (name "unconnected-(IC3-GPIO21-Pad27)") (class "Default")
      (node (ref "IC3") (pin "27") (pinfunction "GPIO21_27") (pintype "passive+no_connect"))
    )
    (net (code "50") (name "unconnected-(IC3-GPIO33-Pad38)") (class "Default")
      (node (ref "IC3") (pin "38") (pinfunction "GPIO33_38") (pintype "passive+no_connect"))
    )
    (net (code "51") (name "unconnected-(IC3-GPIO34-Pad39)") (class "Default")
      (node (ref "IC3") (pin "39") (pinfunction "GPIO34_39") (pintype "passive+no_connect"))
    )
    (net (code "52") (name "unconnected-(IC3-GPIO35-Pad40)") (class "Default")
      (node (ref "IC3") (pin "40") (pinfunction "GPIO35_40") (pintype "passive+no_connect"))
    )
    (net (code "53") (name "unconnected-(IC3-GPIO36-Pad41)") (class "Default")
      (node (ref "IC3") (pin "41") (pinfunction "GPIO36_41") (pintype "passive+no_connect"))
    )
    (net (code "54") (name "unconnected-(IC3-GPIO37-Pad42)") (class "Default")
      (node (ref "IC3") (pin "42") (pinfunction "GPIO37_42") (pintype "passive+no_connect"))
    )
    (net (code "55") (name "unconnected-(IC3-GPIO38-Pad43)") (class "Default")
      (node (ref "IC3") (pin "43") (pinfunction "GPIO38_43") (pintype "passive+no_connect"))
    )
    (net (code "56") (name "unconnected-(IC3-GPIO46-Pad52)") (class "Default")
      (node (ref "IC3") (pin "52") (pinfunction "GPIO46_52") (pintype "passive+no_connect"))
    )
    (net (code "57") (name "unconnected-(IC3-NC-Pad30)") (class "Default")
      (node (ref "IC3") (pin "30") (pinfunction "NC_30") (pintype "passive+no_connect"))
    )
    (net (code "58") (name "unconnected-(IC3-NC-Pad31)") (class "Default")
      (node (ref "IC3") (pin "31") (pinfunction "NC_31") (pintype "passive+no_connect"))
    )
    (net (code "59") (name "unconnected-(IC3-NC-Pad32)") (class "Default")
      (node (ref "IC3") (pin "32") (pinfunction "NC_32") (pintype "passive+no_connect"))
    )
    (net (code "60") (name "unconnected-(IC3-NC-Pad33)") (class "Default")
      (node (ref "IC3") (pin "33") (pinfunction "NC_33") (pintype "passive+no_connect"))
    )
    (net (code "61") (name "unconnected-(IC3-NC-Pad34)") (class "Default")
      (node (ref "IC3") (pin "34") (pinfunction "NC_34") (pintype "passive+no_connect"))
    )
    (net (code "62") (name "unconnected-(IC3-NC-Pad35)") (class "Default")
      (node (ref "IC3") (pin "35") (pinfunction "NC_35") (pintype "passive+no_connect"))
    )
    (net (code "63") (name "unconnected-(IC3-NC-Pad53)") (class "Default")
      (node (ref "IC3") (pin "53") (pinfunction "NC_53") (pintype "passive+no_connect"))
    )
    (net (code "64") (name "unconnected-(IC3-NC-Pad54)") (class "Default")
      (node (ref "IC3") (pin "54") (pinfunction "NC_54") (pintype "passive+no_connect"))
    )
    (net (code "65") (name "unconnected-(IC3-SPICLK_N-Pad36)") (class "Default")
      (node (ref "IC3") (pin "36") (pinfunction "SPICLK_N_36") (pintype "passive+no_connect"))
    )
    (net (code "66") (name "unconnected-(IC3-SPICLK_P-Pad37)") (class "Default")
      (node (ref "IC3") (pin "37") (pinfunction "SPICLK_P_37") (pintype "passive+no_connect"))
    )
    (net (code "67") (name "unconnected-(IC3-SPICS1-Pad28)") (class "Default")
      (node (ref "IC3") (pin "28") (pinfunction "SPICS1_28") (pintype "passive+no_connect"))
    )
    (net (code "68") (name "unconnected-(IC3-VDD_SPI-Pad29)") (class "Default")
      (node (ref "IC3") (pin "29") (pinfunction "VDD_SPI_29") (pintype "passive+no_connect"))
    )
    (net (code "69") (name "unconnected-(LED2-DO-Pad1)") (class "Default")
      (node (ref "LED2") (pin "1") (pinfunction "DO_1") (pintype "passive+no_connect"))
    )
    (net (code "70") (name "unconnected-(USB-RX1N-PadB10)") (class "Default")
      (node (ref "USB") (pin "B10") (pinfunction "RX1N_B10") (pintype "passive+no_connect"))
    )
    (net (code "71") (name "unconnected-(USB-RX1P-PadB11)") (class "Default")
      (node (ref "USB") (pin "B11") (pinfunction "RX1P_B11") (pintype "passive+no_connect"))
    )
    (net (code "72") (name "unconnected-(USB-RX2N-PadA10)") (class "Default")
      (node (ref "USB") (pin "A10") (pinfunction "RX2N_A10") (pintype "passive+no_connect"))
    )
    (net (code "73") (name "unconnected-(USB-RX2P-PadA11)") (class "Default")
      (node (ref "USB") (pin "A11") (pinfunction "RX2P_A11") (pintype "passive+no_connect"))
    )
    (net (code "74") (name "unconnected-(USB-SBU1-PadA8)") (class "Default")
      (node (ref "USB") (pin "A8") (pinfunction "SBU1_A8") (pintype "passive+no_connect"))
    )
    (net (code "75") (name "unconnected-(USB-SBU2-PadB8)") (class "Default")
      (node (ref "USB") (pin "B8") (pinfunction "SBU2_B8") (pintype "passive+no_connect"))
    )
    (net (code "76") (name "unconnected-(USB-TX1N-PadA3)") (class "Default")
      (node (ref "USB") (pin "A3") (pinfunction "TX1N_A3") (pintype "passive+no_connect"))
    )
    (net (code "77") (name "unconnected-(USB-TX1P-PadA2)") (class "Default")
      (node (ref "USB") (pin "A2") (pinfunction "TX1P_A2") (pintype "passive+no_connect"))
    )
    (net (code "78") (name "unconnected-(USB-TX2N-PadB3)") (class "Default")
      (node (ref "USB") (pin "B3") (pinfunction "TX2N_B3") (pintype "passive+no_connect"))
    )
    (net (code "79") (name "unconnected-(USB-TX2P-PadB2)") (class "Default")
      (node (ref "USB") (pin "B2") (pinfunction "TX2P_B2") (pintype "passive+no_connect"))
    )
  )
)
